# Display_BBM.net
KiCad netlist of a schematic drawn in EAGLE
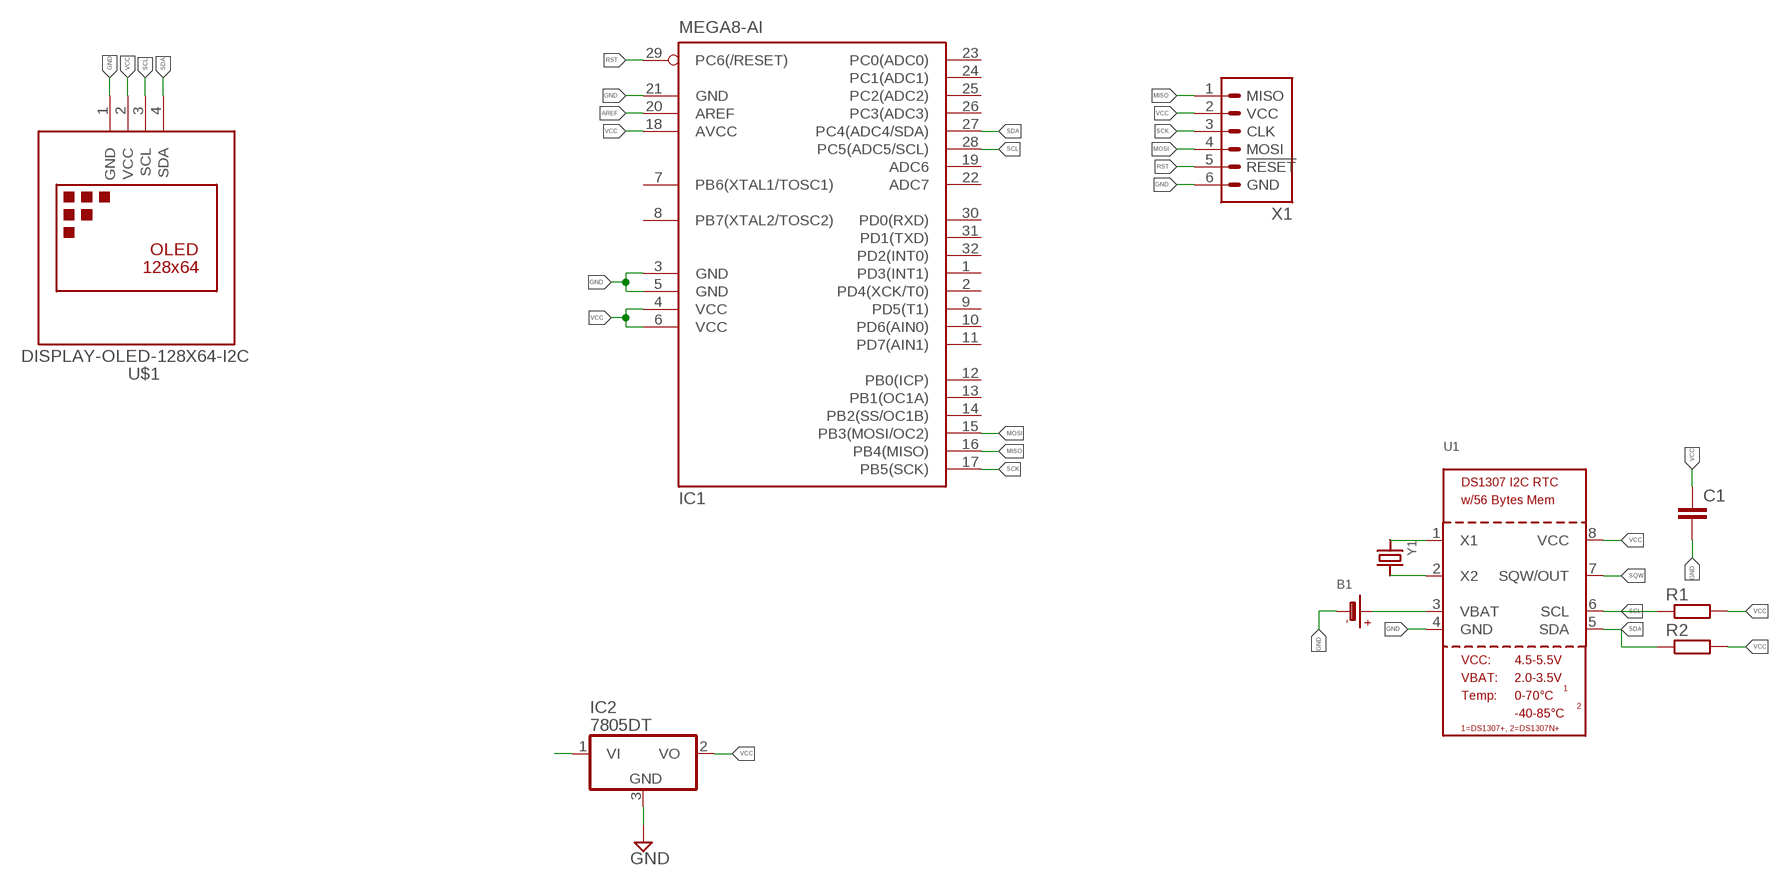
[diagram p0: schematic, sheet 1]

(export (version "E")
  (design (tool "Eeschema 10.0.6"))
  (components
    (comp (ref "B1")
      (value "BATTERYCR1220_SMT")
      (footprint "eagle-import:CR1220")
      (libsource (lib "eagle-import") (part "BATTERYCR1220_SMT"))
    )
    (comp (ref "C1")
      (value "C-EUC0603K")
      (footprint "eagle-import:C0603K")
      (libsource (lib "eagle-import") (part "C-EUC0603K"))
    )
    (comp (ref "IC1")
      (value "MEGA8-AI")
      (footprint "eagle-import:TQFP32-08")
      (fields (field (name "MPN") "ATMEGA8-16AU"))
      (libsource (lib "eagle-import") (part "MEGA8-AI"))
    )
    (comp (ref "IC2")
      (value "7805DT")
      (footprint "eagle-import:TO252")
      (libsource (lib "eagle-import") (part "78DT05"))
    )
    (comp (ref "R1")
      (value "R-EU_R0603")
      (footprint "eagle-import:R0603")
      (libsource (lib "eagle-import") (part "R-EU_R0603"))
    )
    (comp (ref "R2")
      (value "R-EU_R0603")
      (footprint "eagle-import:R0603")
      (libsource (lib "eagle-import") (part "R-EU_R0603"))
    )
    (comp (ref "U$1")
      (value "DISPLAY-OLED-128X64-I2C")
      (footprint "eagle-import:DISPLAY-OLED-128X64-I2C")
      (libsource (lib "eagle-import") (part "DISPLAY-OLED-128X64-I2C"))
    )
    (comp (ref "U1")
      (value "RTC_DS1307")
      (footprint "eagle-import:SOIC8_150MIL")
      (libsource (lib "eagle-import") (part "RTC_DS1307"))
    )
    (comp (ref "X1")
      (value "MISO_MOSIIDC-06V")
      (footprint "eagle-import:IDC-06V")
      (libsource (lib "eagle-import") (part "MISO_MOSIIDC-06V"))
    )
    (comp (ref "Y1")
      (value "CRYSTAL8.0X3.8")
      (footprint "eagle-import:CRYSTAL_8X3.8")
      (libsource (lib "eagle-import") (part "CRYSTAL8.0X3.8"))
    )
  )
  (nets
    (net (code "1") (name "AREF") (class "Default")
      (node (ref "IC1") (pin "20") (pinfunction "AREF_20") (pintype "passive"))
    )
    (net (code "2") (name "GND") (class "Default")
      (node (ref "B1") (pin "-") (pinfunction "-_-") (pintype "passive"))
      (node (ref "C1") (pin "2") (pinfunction "2_2") (pintype "passive"))
      (node (ref "IC1") (pin "21") (pinfunction "GND_21") (pintype "power_in"))
      (node (ref "IC1") (pin "3") (pinfunction "GND_3") (pintype "power_in"))
      (node (ref "IC1") (pin "5") (pinfunction "GND_5") (pintype "power_in"))
      (node (ref "IC2") (pin "3") (pinfunction "GND_3") (pintype "passive"))
      (node (ref "U$1") (pin "1") (pinfunction "GND_1") (pintype "power_in"))
      (node (ref "U1") (pin "4") (pinfunction "GND_4") (pintype "bidirectional"))
      (node (ref "X1") (pin "6") (pinfunction "GND_6") (pintype "power_in"))
    )
    (net (code "3") (name "MISO") (class "Default")
      (node (ref "IC1") (pin "16") (pinfunction "PB4(MISO)_16") (pintype "bidirectional"))
      (node (ref "X1") (pin "1") (pinfunction "MISO_1") (pintype "passive"))
    )
    (net (code "4") (name "MOSI") (class "Default")
      (node (ref "IC1") (pin "15") (pinfunction "PB3(MOSI/OC2)_15") (pintype "bidirectional"))
      (node (ref "X1") (pin "4") (pinfunction "MOSI_4") (pintype "passive"))
    )
    (net (code "5") (name "Net-(B1-+)") (class "Default")
      (node (ref "B1") (pin "+$1") (pinfunction "+_+$1") (pintype "passive"))
      (node (ref "U1") (pin "3") (pinfunction "VBAT_3") (pintype "bidirectional"))
    )
    (net (code "6") (name "Net-(U1-X1)") (class "Default")
      (node (ref "U1") (pin "1") (pinfunction "X1_1") (pintype "bidirectional"))
      (node (ref "Y1") (pin "P$1") (pinfunction "1_P$1") (pintype "passive"))
    )
    (net (code "7") (name "Net-(U1-X2)") (class "Default")
      (node (ref "U1") (pin "2") (pinfunction "X2_2") (pintype "bidirectional"))
      (node (ref "Y1") (pin "P$4") (pinfunction "2_P$4") (pintype "passive"))
    )
    (net (code "8") (name "RST") (class "Default")
      (node (ref "IC1") (pin "29") (pinfunction "PC6(/RESET)_29") (pintype "bidirectional"))
      (node (ref "X1") (pin "5") (pinfunction "~{RESET}_5") (pintype "passive"))
    )
    (net (code "9") (name "SCK") (class "Default")
      (node (ref "IC1") (pin "17") (pinfunction "PB5(SCK)_17") (pintype "bidirectional"))
      (node (ref "X1") (pin "3") (pinfunction "CLK_3") (pintype "passive"))
    )
    (net (code "10") (name "SCL") (class "Default")
      (node (ref "IC1") (pin "28") (pinfunction "PC5(ADC5/SCL)_28") (pintype "bidirectional"))
      (node (ref "R1") (pin "1") (pinfunction "1_1") (pintype "passive"))
      (node (ref "U$1") (pin "3") (pinfunction "SCL_3") (pintype "bidirectional"))
      (node (ref "U1") (pin "6") (pinfunction "SCL_6") (pintype "bidirectional"))
    )
    (net (code "11") (name "SDA") (class "Default")
      (node (ref "IC1") (pin "27") (pinfunction "PC4(ADC4/SDA)_27") (pintype "bidirectional"))
      (node (ref "R2") (pin "1") (pinfunction "1_1") (pintype "passive"))
      (node (ref "U$1") (pin "4") (pinfunction "SDA_4") (pintype "bidirectional"))
      (node (ref "U1") (pin "5") (pinfunction "SDA_5") (pintype "bidirectional"))
    )
    (net (code "12") (name "SQW") (class "Default")
      (node (ref "U1") (pin "7") (pinfunction "SQW/OUT_7") (pintype "bidirectional"))
    )
    (net (code "13") (name "VCC") (class "Default")
      (node (ref "C1") (pin "1") (pinfunction "1_1") (pintype "passive"))
      (node (ref "IC1") (pin "18") (pinfunction "AVCC_18") (pintype "power_in"))
      (node (ref "IC1") (pin "4") (pinfunction "VCC_4") (pintype "power_in"))
      (node (ref "IC1") (pin "6") (pinfunction "VCC_6") (pintype "power_in"))
      (node (ref "IC2") (pin "2") (pinfunction "VO_2") (pintype "passive"))
      (node (ref "R1") (pin "2") (pinfunction "2_2") (pintype "passive"))
      (node (ref "R2") (pin "2") (pinfunction "2_2") (pintype "passive"))
      (node (ref "U$1") (pin "2") (pinfunction "VCC_2") (pintype "power_in"))
      (node (ref "U1") (pin "8") (pinfunction "VCC_8") (pintype "bidirectional"))
      (node (ref "X1") (pin "2") (pinfunction "VCC_2") (pintype "power_in"))
    )
    (net (code "14") (name "unconnected-(IC1-ADC6-Pad19)") (class "Default")
      (node (ref "IC1") (pin "19") (pinfunction "ADC6_19") (pintype "bidirectional"))
    )
    (net (code "15") (name "unconnected-(IC1-ADC7-Pad22)") (class "Default")
      (node (ref "IC1") (pin "22") (pinfunction "ADC7_22") (pintype "bidirectional"))
    )
    (net (code "16") (name "unconnected-(IC1-PB0(ICP)-Pad12)") (class "Default")
      (node (ref "IC1") (pin "12") (pinfunction "PB0(ICP)_12") (pintype "bidirectional"))
    )
    (net (code "17") (name "unconnected-(IC1-PB1(OC1A)-Pad13)") (class "Default")
      (node (ref "IC1") (pin "13") (pinfunction "PB1(OC1A)_13") (pintype "bidirectional"))
    )
    (net (code "18") (name "unconnected-(IC1-PB2(SS{slash}OC1B)-Pad14)") (class "Default")
      (node (ref "IC1") (pin "14") (pinfunction "PB2(SS/OC1B)_14") (pintype "bidirectional"))
    )
    (net (code "19") (name "unconnected-(IC1-PB6(XTAL1{slash}TOSC1)-Pad7)") (class "Default")
      (node (ref "IC1") (pin "7") (pinfunction "PB6(XTAL1/TOSC1)_7") (pintype "bidirectional"))
    )
    (net (code "20") (name "unconnected-(IC1-PB7(XTAL2{slash}TOSC2)-Pad8)") (class "Default")
      (node (ref "IC1") (pin "8") (pinfunction "PB7(XTAL2/TOSC2)_8") (pintype "bidirectional"))
    )
    (net (code "21") (name "unconnected-(IC1-PC0(ADC0)-Pad23)") (class "Default")
      (node (ref "IC1") (pin "23") (pinfunction "PC0(ADC0)_23") (pintype "bidirectional"))
    )
    (net (code "22") (name "unconnected-(IC1-PC1(ADC1)-Pad24)") (class "Default")
      (node (ref "IC1") (pin "24") (pinfunction "PC1(ADC1)_24") (pintype "bidirectional"))
    )
    (net (code "23") (name "unconnected-(IC1-PC2(ADC2)-Pad25)") (class "Default")
      (node (ref "IC1") (pin "25") (pinfunction "PC2(ADC2)_25") (pintype "bidirectional"))
    )
    (net (code "24") (name "unconnected-(IC1-PC3(ADC3)-Pad26)") (class "Default")
      (node (ref "IC1") (pin "26") (pinfunction "PC3(ADC3)_26") (pintype "bidirectional"))
    )
    (net (code "25") (name "unconnected-(IC1-PD0(RXD)-Pad30)") (class "Default")
      (node (ref "IC1") (pin "30") (pinfunction "PD0(RXD)_30") (pintype "bidirectional"))
    )
    (net (code "26") (name "unconnected-(IC1-PD1(TXD)-Pad31)") (class "Default")
      (node (ref "IC1") (pin "31") (pinfunction "PD1(TXD)_31") (pintype "bidirectional"))
    )
    (net (code "27") (name "unconnected-(IC1-PD2(INT0)-Pad32)") (class "Default")
      (node (ref "IC1") (pin "32") (pinfunction "PD2(INT0)_32") (pintype "bidirectional"))
    )
    (net (code "28") (name "unconnected-(IC1-PD3(INT1)-Pad1)") (class "Default")
      (node (ref "IC1") (pin "1") (pinfunction "PD3(INT1)_1") (pintype "bidirectional"))
    )
    (net (code "29") (name "unconnected-(IC1-PD4(XCK{slash}T0)-Pad2)") (class "Default")
      (node (ref "IC1") (pin "2") (pinfunction "PD4(XCK/T0)_2") (pintype "bidirectional"))
    )
    (net (code "30") (name "unconnected-(IC1-PD5(T1)-Pad9)") (class "Default")
      (node (ref "IC1") (pin "9") (pinfunction "PD5(T1)_9") (pintype "bidirectional"))
    )
    (net (code "31") (name "unconnected-(IC1-PD6(AIN0)-Pad10)") (class "Default")
      (node (ref "IC1") (pin "10") (pinfunction "PD6(AIN0)_10") (pintype "bidirectional"))
    )
    (net (code "32") (name "unconnected-(IC1-PD7(AIN1)-Pad11)") (class "Default")
      (node (ref "IC1") (pin "11") (pinfunction "PD7(AIN1)_11") (pintype "bidirectional"))
    )
    (net (code "33") (name "unconnected-(IC2-VI-Pad1)") (class "Default")
      (node (ref "IC2") (pin "1") (pinfunction "VI_1") (pintype "input"))
    )
  )
)
